# Cell.net
KiCad netlist of a schematic drawn in Altium Designer
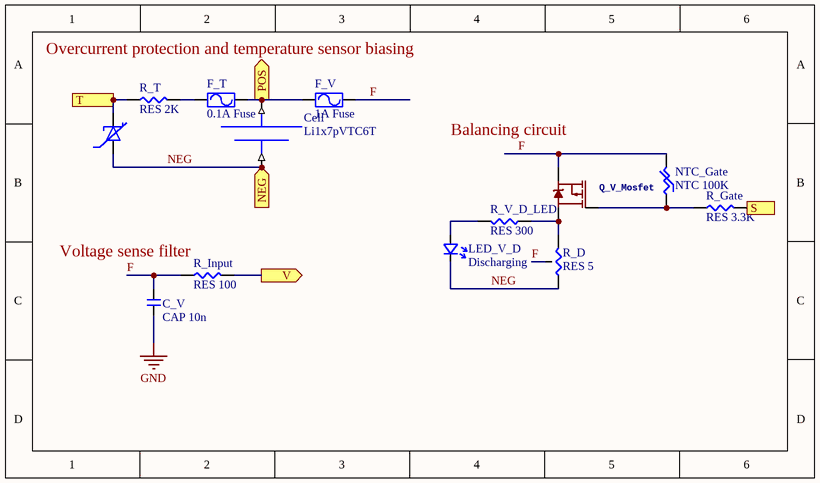
[diagram p0: Cell.SchDoc]

(export (version "E")
  (design (tool "Eeschema 10.0.6"))
  (components
    (comp (ref "Cell")
      (value "Li1x7pVTC6T")
      (footprint "Li1x7pVTC6T")
      (libsource (lib "ife18_TS_BMS_LTC6813_v2_Library") (part "Li1x7pVTC6T"))
    )
    (comp (ref "C_V")
      (value "CAP 10n")
      (footprint "CAP-0603")
      (description "CAP-0603")
      (libsource (lib "altium-import") (part "root_1_CAP-0603_"))
    )
    (comp (ref "F_T")
      (value "0.1A Fuse")
      (footprint "2410SMD")
      (description "0679L")
      (libsource (lib "altium-import") (part "root_0_0679L_"))
    )
    (comp (ref "F_V")
      (value "1A Fuse")
      (footprint "2410SMD")
      (description "0679L")
      (libsource (lib "altium-import") (part "root_0_0679L_"))
    )
    (comp (ref "LED_V_D")
      (value "Discharging")
      (footprint "LED-0603")
      (description "LED-0603")
      (libsource (lib "altium-import") (part "root_3_LED-0603_"))
    )
    (comp (ref "NTC_Gate")
      (value "NTC 100K")
      (footprint "NTC-0603")
      (description "NTC-0603")
      (libsource (lib "altium-import") (part "root_1_NTC-0603_"))
    )
    (comp (ref "Q_V_Mosfet")
      (value "~")
      (footprint "TO252")
      (description "DMP10H400SK3-13")
      (libsource (lib "altium-import") (part "root_0_DMP10H400SK3-13_"))
    )
    (comp (ref "R_D")
      (value "RES 5")
      (footprint "TO252-TKH-45")
      (description "TKH45")
      (libsource (lib "altium-import") (part "root_1_TKH45_"))
    )
    (comp (ref "R_Gate")
      (value "RES 3.3K")
      (footprint "RES-0603")
      (libsource (lib "altium-import") (part "root_0_RES-0603_"))
    )
    (comp (ref "R_Input")
      (value "RES 100")
      (footprint "RES-0603")
      (libsource (lib "altium-import") (part "root_0_RES-0603_"))
    )
    (comp (ref "R_T")
      (value "RES 2K")
      (footprint "RES-0603")
      (libsource (lib "altium-import") (part "root_0_RES-0603_"))
    )
    (comp (ref "R_V_D_LED")
      (value "RES 300")
      (footprint "RES-0603")
      (libsource (lib "altium-import") (part "root_2_RES-0603_"))
    )
  )
  (nets
    (net (code "1") (name "/F") (class "Default")
      (node (ref "C_V") (pin "2") (pinfunction "2_2") (pintype "passive"))
      (node (ref "F_V") (pin "1") (pinfunction "1_1") (pintype "passive"))
      (node (ref "NTC_Gate") (pin "2") (pinfunction "2_2") (pintype "passive"))
      (node (ref "Q_V_Mosfet") (pin "3") (pinfunction "S_3") (pintype "passive"))
      (node (ref "R_D") (pin "3") (pinfunction "3_3") (pintype "passive"))
      (node (ref "R_Input") (pin "1") (pinfunction "1_1") (pintype "passive"))
    )
    (net (code "2") (name "/NEG") (class "Default")
      (node (ref "Cell") (pin "-") (pinfunction "-_-") (pintype "input"))
      (node (ref "Cell") (pin "T-") (pinfunction "T-_T-") (pintype "passive"))
      (node (ref "LED_V_D") (pin "K") (pinfunction "K_K") (pintype "passive"))
      (node (ref "R_D") (pin "1") (pinfunction "1_1") (pintype "passive"))
    )
    (net (code "3") (name "/POS") (class "Default")
      (node (ref "Cell") (pin "+") (pinfunction "+_+") (pintype "output"))
      (node (ref "F_T") (pin "1") (pinfunction "1_1") (pintype "passive"))
      (node (ref "F_V") (pin "2") (pinfunction "2_2") (pintype "passive"))
    )
    (net (code "4") (name "/S") (class "Default")
      (node (ref "R_Gate") (pin "2") (pinfunction "2_2") (pintype "passive"))
    )
    (net (code "5") (name "/T") (class "Default")
      (node (ref "Cell") (pin "T+") (pinfunction "T+_T+") (pintype "passive"))
      (node (ref "R_T") (pin "1") (pinfunction "1_1") (pintype "passive"))
    )
    (net (code "6") (name "/V") (class "Default")
      (node (ref "R_Input") (pin "2") (pinfunction "2_2") (pintype "passive"))
    )
    (net (code "7") (name "GND") (class "Default")
      (node (ref "C_V") (pin "1") (pinfunction "1_1") (pintype "passive"))
    )
    (net (code "8") (name "Net-(F_T-Pad2)") (class "Default")
      (node (ref "F_T") (pin "2") (pinfunction "2_2") (pintype "passive"))
      (node (ref "R_T") (pin "2") (pinfunction "2_2") (pintype "passive"))
    )
    (net (code "9") (name "Net-(LED_V_D-PadA)") (class "Default")
      (node (ref "LED_V_D") (pin "A") (pinfunction "A_A") (pintype "passive"))
      (node (ref "R_V_D_LED") (pin "2") (pinfunction "2_2") (pintype "passive"))
    )
    (net (code "10") (name "Net-(Q_V_Mosfet-D)") (class "Default")
      (node (ref "Q_V_Mosfet") (pin "2") (pinfunction "D_2") (pintype "passive"))
      (node (ref "R_D") (pin "2") (pinfunction "2_2") (pintype "passive"))
      (node (ref "R_V_D_LED") (pin "1") (pinfunction "1_1") (pintype "passive"))
    )
    (net (code "11") (name "Net-(Q_V_Mosfet-G)") (class "Default")
      (node (ref "NTC_Gate") (pin "1") (pinfunction "1_1") (pintype "passive"))
      (node (ref "Q_V_Mosfet") (pin "1") (pinfunction "G_1") (pintype "passive"))
      (node (ref "R_Gate") (pin "1") (pinfunction "1_1") (pintype "passive"))
    )
  )
)
